# diskohedron4w_revd.net
KiCad netlist of a schematic drawn in EAGLE
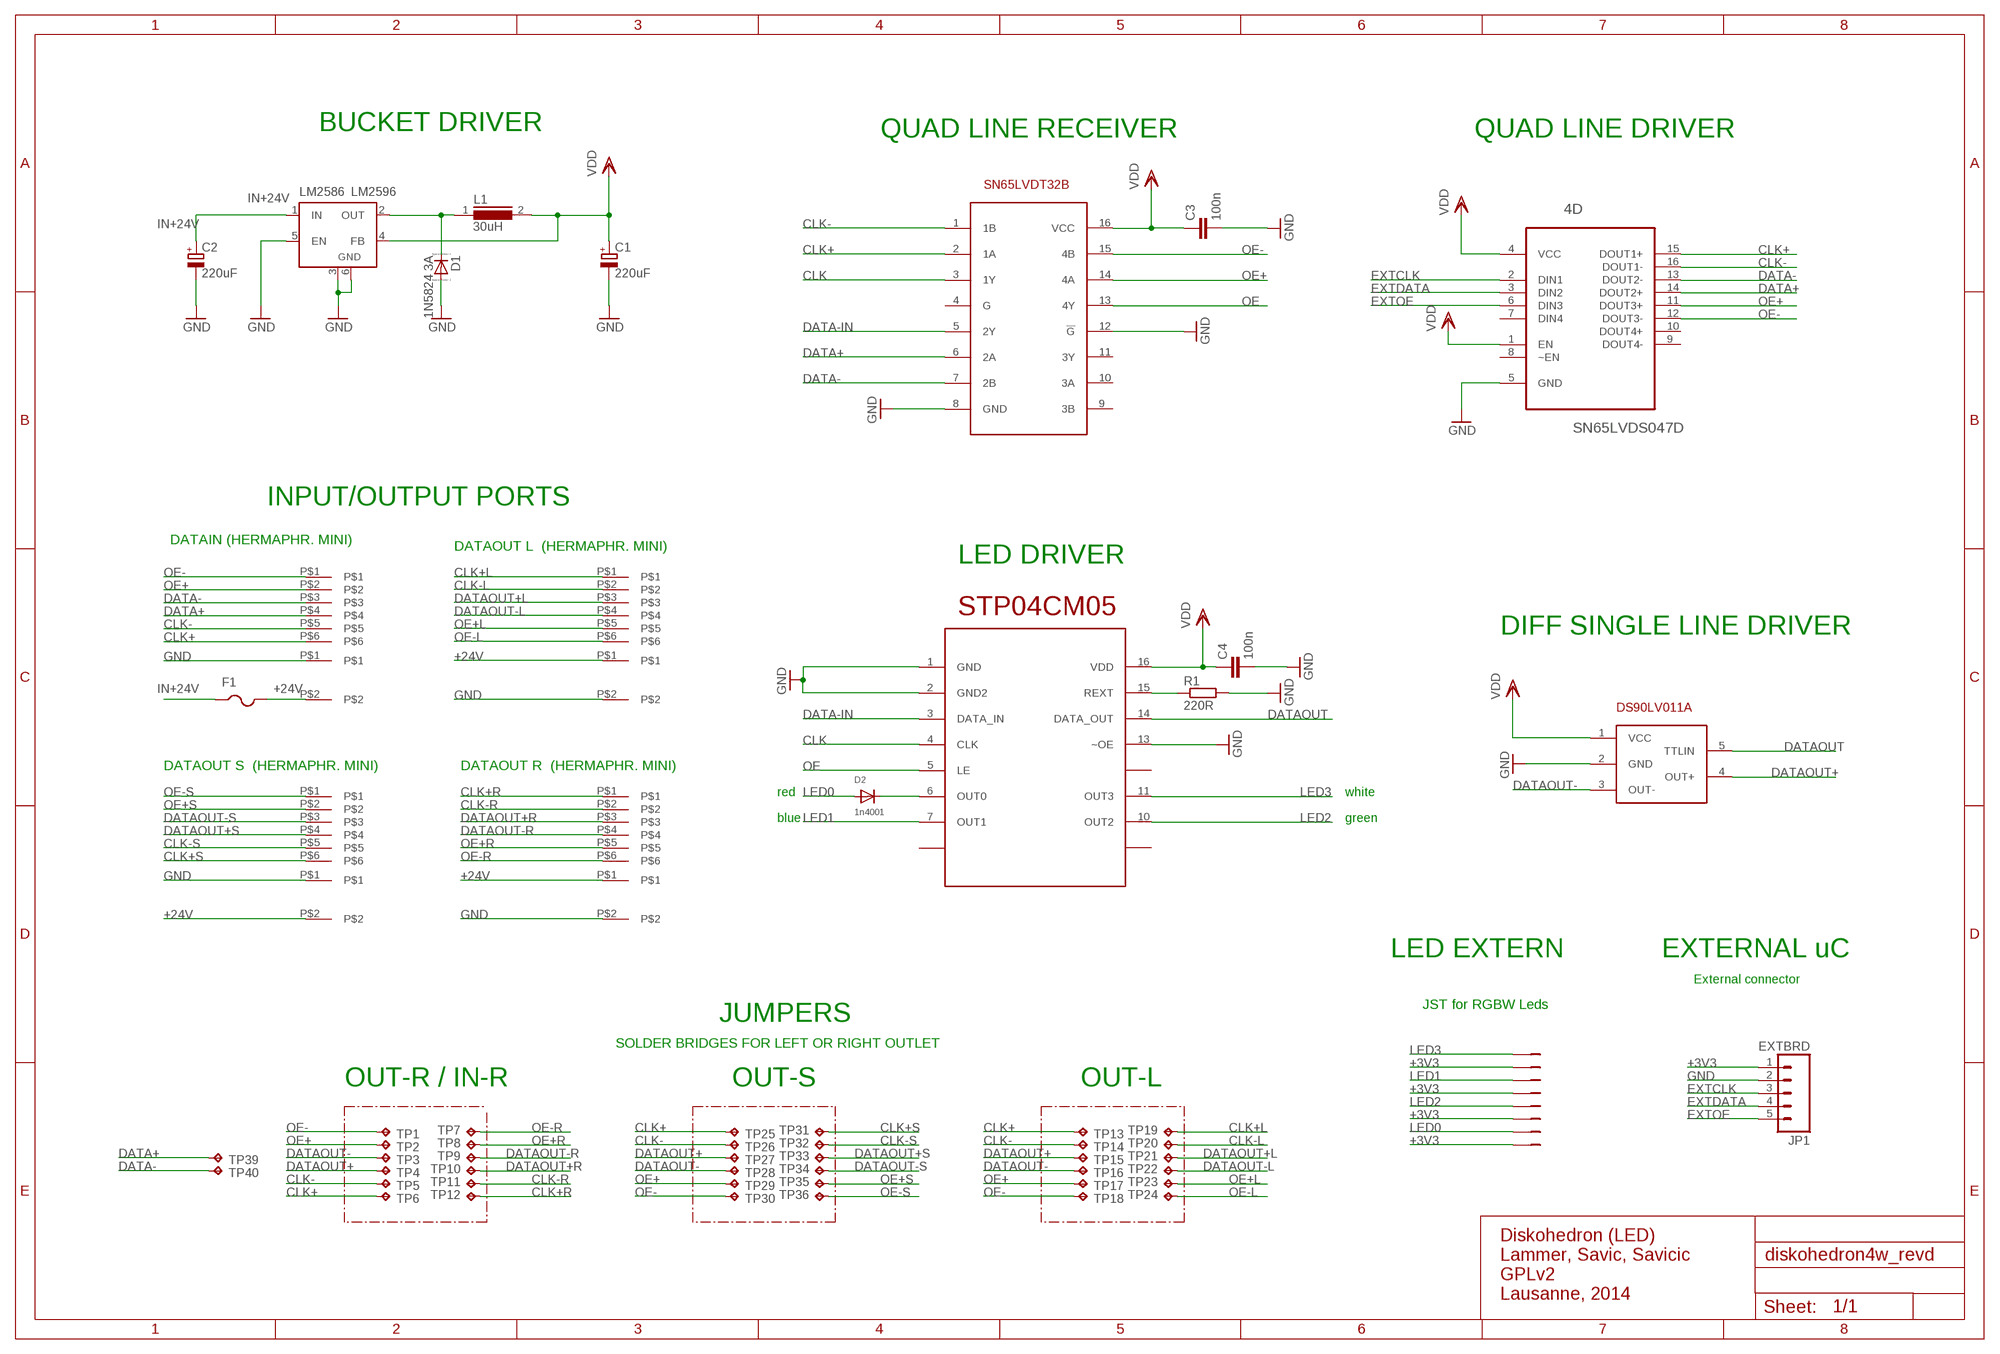
[diagram p0: schematic, sheet 1]

(export (version "E")
  (design (tool "Eeschema 10.0.6"))
  (components
    (comp (ref "1D")
      (value "DS90LV011A")
      (footprint "eagle-import:SOT23-5")
      (libsource (lib "eagle-import") (part "DS90LV011A"))
    )
    (comp (ref "4D")
      (value "SN65LVDS047D")
      (footprint "eagle-import:SOIC127P600X175-16N")
      (libsource (lib "eagle-import") (part "SN65LVDS047D"))
    )
    (comp (ref "4R")
      (value "SN65LVDST32")
      (footprint "eagle-import:SOIC16")
      (libsource (lib "eagle-import") (part "SN65LVDST32"))
    )
    (comp (ref "C1")
      (value "220uF")
      (footprint "eagle-import:175TMP-0810")
      (libsource (lib "eagle-import") (part "CPOL-EU175TMP-0810"))
    )
    (comp (ref "C2")
      (value "220uF")
      (footprint "eagle-import:175TMP-0810")
      (libsource (lib "eagle-import") (part "CPOL-EU175TMP-0810"))
    )
    (comp (ref "C3")
      (value "100n")
      (footprint "eagle-import:C0805")
      (libsource (lib "eagle-import") (part "C-EUC0805"))
    )
    (comp (ref "C4")
      (value "100n")
      (footprint "eagle-import:C0805")
      (libsource (lib "eagle-import") (part "C-EUC0805"))
    )
    (comp (ref "D1")
      (value "1N5824 3A")
      (footprint "eagle-import:DIODE_SMC")
      (libsource (lib "eagle-import") (part "DIODE_E-SMC"))
    )
    (comp (ref "D2")
      (value "1n4001")
      (footprint "eagle-import:SMADIODE")
      (libsource (lib "eagle-import") (part "DIODESMA"))
    )
    (comp (ref "F1")
      (value "PTCFUSE-1812")
      (footprint "eagle-import:1812")
      (libsource (lib "eagle-import") (part "PTCFUSE-1812"))
    )
    (comp (ref "IN1")
      (value "HERMAPHRODITMINI6PIN")
      (footprint "eagle-import:HERMAPHRODITMINI6PIN")
      (libsource (lib "eagle-import") (part "HERMAPHRODITMINI6PIN"))
    )
    (comp (ref "JP1")
      (value "EXTBRD")
      (footprint "eagle-import:1X05")
      (libsource (lib "eagle-import") (part "M05PTH"))
    )
    (comp (ref "JST")
      (value "8PIN-ZH")
      (footprint "eagle-import:B8B-ZH")
      (libsource (lib "eagle-import") (part "8PIN-ZH"))
    )
    (comp (ref "L1")
      (value "30uH")
      (footprint "eagle-import:DR127")
      (libsource (lib "eagle-import") (part "DR127"))
    )
    (comp (ref "LM2586")
      (value "LM2596")
      (footprint "eagle-import:TO263-5")
      (libsource (lib "eagle-import") (part "LM2596S"))
    )
    (comp (ref "OUT-L")
      (value "HERMAPHRODITMINI6PIN")
      (footprint "eagle-import:HERMAPHRODITMINI6PIN")
      (libsource (lib "eagle-import") (part "HERMAPHRODITMINI6PIN"))
    )
    (comp (ref "OUT-R")
      (value "HERMAPHRODITMINI6PIN")
      (footprint "eagle-import:HERMAPHRODITMINI6PIN")
      (libsource (lib "eagle-import") (part "HERMAPHRODITMINI6PIN"))
    )
    (comp (ref "OUT-R1")
      (value "HERMAPHRODITMINI6PIN")
      (footprint "eagle-import:HERMAPHRODITMINI6PIN")
      (libsource (lib "eagle-import") (part "HERMAPHRODITMINI6PIN"))
    )
    (comp (ref "R1")
      (value "220R")
      (footprint "eagle-import:M0805")
      (libsource (lib "eagle-import") (part "R-EU_M0805"))
    )
    (comp (ref "STP04")
      (value "STP04CM05")
      (footprint "eagle-import:TSSOP16")
      (libsource (lib "eagle-import") (part "STP04CM05"))
    )
    (comp (ref "TP1")
      (value "TPTP12SQ")
      (footprint "eagle-import:TP12SQ")
      (libsource (lib "eagle-import") (part "TPTP12SQ"))
    )
    (comp (ref "TP2")
      (value "TPTP12SQ")
      (footprint "eagle-import:TP12SQ")
      (libsource (lib "eagle-import") (part "TPTP12SQ"))
    )
    (comp (ref "TP3")
      (value "TPTP09SQ")
      (footprint "eagle-import:TP09SQ")
      (libsource (lib "eagle-import") (part "TPTP09SQ"))
    )
    (comp (ref "TP4")
      (value "TPTP09SQ")
      (footprint "eagle-import:TP09SQ")
      (libsource (lib "eagle-import") (part "TPTP09SQ"))
    )
    (comp (ref "TP5")
      (value "TPTP12SQ")
      (footprint "eagle-import:TP12SQ")
      (libsource (lib "eagle-import") (part "TPTP12SQ"))
    )
    (comp (ref "TP6")
      (value "TPTP12SQ")
      (footprint "eagle-import:TP12SQ")
      (libsource (lib "eagle-import") (part "TPTP12SQ"))
    )
    (comp (ref "TP7")
      (value "TPTP12SQ")
      (footprint "eagle-import:TP12SQ")
      (libsource (lib "eagle-import") (part "TPTP12SQ"))
    )
    (comp (ref "TP8")
      (value "TPTP12SQ")
      (footprint "eagle-import:TP12SQ")
      (libsource (lib "eagle-import") (part "TPTP12SQ"))
    )
    (comp (ref "TP9")
      (value "TPTP20SQ")
      (footprint "eagle-import:TP20SQ")
      (libsource (lib "eagle-import") (part "TPTP20SQ"))
    )
    (comp (ref "TP10")
      (value "TPTP20SQ")
      (footprint "eagle-import:TP20SQ")
      (libsource (lib "eagle-import") (part "TPTP20SQ"))
    )
    (comp (ref "TP11")
      (value "TPTP12SQ")
      (footprint "eagle-import:TP12SQ")
      (libsource (lib "eagle-import") (part "TPTP12SQ"))
    )
    (comp (ref "TP12")
      (value "TPTP12SQ")
      (footprint "eagle-import:TP12SQ")
      (libsource (lib "eagle-import") (part "TPTP12SQ"))
    )
    (comp (ref "TP13")
      (value "TPTP12SQ")
      (footprint "eagle-import:TP12SQ")
      (libsource (lib "eagle-import") (part "TPTP12SQ"))
    )
    (comp (ref "TP14")
      (value "TPTP12SQ")
      (footprint "eagle-import:TP12SQ")
      (libsource (lib "eagle-import") (part "TPTP12SQ"))
    )
    (comp (ref "TP15")
      (value "TPTP12SQ")
      (footprint "eagle-import:TP12SQ")
      (libsource (lib "eagle-import") (part "TPTP12SQ"))
    )
    (comp (ref "TP16")
      (value "TPTP12SQ")
      (footprint "eagle-import:TP12SQ")
      (libsource (lib "eagle-import") (part "TPTP12SQ"))
    )
    (comp (ref "TP17")
      (value "TPTP12SQ")
      (footprint "eagle-import:TP12SQ")
      (libsource (lib "eagle-import") (part "TPTP12SQ"))
    )
    (comp (ref "TP18")
      (value "TPTP12SQ")
      (footprint "eagle-import:TP12SQ")
      (libsource (lib "eagle-import") (part "TPTP12SQ"))
    )
    (comp (ref "TP19")
      (value "TPTP12SQ")
      (footprint "eagle-import:TP12SQ")
      (libsource (lib "eagle-import") (part "TPTP12SQ"))
    )
    (comp (ref "TP20")
      (value "TPTP12SQ")
      (footprint "eagle-import:TP12SQ")
      (libsource (lib "eagle-import") (part "TPTP12SQ"))
    )
    (comp (ref "TP21")
      (value "TPTP12SQ")
      (footprint "eagle-import:TP12SQ")
      (libsource (lib "eagle-import") (part "TPTP12SQ"))
    )
    (comp (ref "TP22")
      (value "TPTP12SQ")
      (footprint "eagle-import:TP12SQ")
      (libsource (lib "eagle-import") (part "TPTP12SQ"))
    )
    (comp (ref "TP23")
      (value "TPTP12SQ")
      (footprint "eagle-import:TP12SQ")
      (libsource (lib "eagle-import") (part "TPTP12SQ"))
    )
    (comp (ref "TP24")
      (value "TPTP12SQ")
      (footprint "eagle-import:TP12SQ")
      (libsource (lib "eagle-import") (part "TPTP12SQ"))
    )
    (comp (ref "TP25")
      (value "TPTP12SQ")
      (footprint "eagle-import:TP12SQ")
      (libsource (lib "eagle-import") (part "TPTP12SQ"))
    )
    (comp (ref "TP26")
      (value "TPTP12SQ")
      (footprint "eagle-import:TP12SQ")
      (libsource (lib "eagle-import") (part "TPTP12SQ"))
    )
    (comp (ref "TP27")
      (value "TPTP12SQ")
      (footprint "eagle-import:TP12SQ")
      (libsource (lib "eagle-import") (part "TPTP12SQ"))
    )
    (comp (ref "TP28")
      (value "TPTP12SQ")
      (footprint "eagle-import:TP12SQ")
      (libsource (lib "eagle-import") (part "TPTP12SQ"))
    )
    (comp (ref "TP29")
      (value "TPTP12SQ")
      (footprint "eagle-import:TP12SQ")
      (libsource (lib "eagle-import") (part "TPTP12SQ"))
    )
    (comp (ref "TP30")
      (value "TPTP12SQ")
      (footprint "eagle-import:TP12SQ")
      (libsource (lib "eagle-import") (part "TPTP12SQ"))
    )
    (comp (ref "TP31")
      (value "TPTP12SQ")
      (footprint "eagle-import:TP12SQ")
      (libsource (lib "eagle-import") (part "TPTP12SQ"))
    )
    (comp (ref "TP32")
      (value "TPTP12SQ")
      (footprint "eagle-import:TP12SQ")
      (libsource (lib "eagle-import") (part "TPTP12SQ"))
    )
    (comp (ref "TP33")
      (value "TPTP12SQ")
      (footprint "eagle-import:TP12SQ")
      (libsource (lib "eagle-import") (part "TPTP12SQ"))
    )
    (comp (ref "TP34")
      (value "TPTP12SQ")
      (footprint "eagle-import:TP12SQ")
      (libsource (lib "eagle-import") (part "TPTP12SQ"))
    )
    (comp (ref "TP35")
      (value "TPTP12SQ")
      (footprint "eagle-import:TP12SQ")
      (libsource (lib "eagle-import") (part "TPTP12SQ"))
    )
    (comp (ref "TP36")
      (value "TPTP12SQ")
      (footprint "eagle-import:TP12SQ")
      (libsource (lib "eagle-import") (part "TPTP12SQ"))
    )
    (comp (ref "TP39")
      (value "TPTP09SQ")
      (footprint "eagle-import:TP09SQ")
      (libsource (lib "eagle-import") (part "TPTP09SQ"))
    )
    (comp (ref "TP40")
      (value "TPTP09SQ")
      (footprint "eagle-import:TP09SQ")
      (libsource (lib "eagle-import") (part "TPTP09SQ"))
    )
    (comp (ref "U$1")
      (value "HERMAPHRODIT2PIN")
      (footprint "eagle-import:HERMAPHRODIT2PIN")
      (libsource (lib "eagle-import") (part "HERMAPHRODIT2PIN"))
    )
    (comp (ref "U$6")
      (value "HERMAPHRODIT2PIN")
      (footprint "eagle-import:HERMAPHRODIT2PIN")
      (libsource (lib "eagle-import") (part "HERMAPHRODIT2PIN"))
    )
    (comp (ref "U$7")
      (value "HERMAPHRODIT2PIN")
      (footprint "eagle-import:HERMAPHRODIT2PIN")
      (libsource (lib "eagle-import") (part "HERMAPHRODIT2PIN"))
    )
    (comp (ref "U$12")
      (value "HERMAPHRODIT2PIN")
      (footprint "eagle-import:HERMAPHRODIT2PIN")
      (libsource (lib "eagle-import") (part "HERMAPHRODIT2PIN"))
    )
  )
  (nets
    (net (code "1") (name "/+24V") (class "Default")
      (node (ref "F1") (pin "2") (pinfunction "2_2") (pintype "passive"))
      (node (ref "U$1") (pin "P$2") (pinfunction "P$2_P$2") (pintype "bidirectional"))
      (node (ref "U$12") (pin "P$1") (pinfunction "P$1_P$1") (pintype "bidirectional"))
      (node (ref "U$6") (pin "P$1") (pinfunction "P$1_P$1") (pintype "bidirectional"))
      (node (ref "U$7") (pin "P$2") (pinfunction "P$2_P$2") (pintype "bidirectional"))
    )
    (net (code "2") (name "/CLK") (class "Default")
      (node (ref "4R") (pin "3") (pinfunction "1Y_3") (pintype "bidirectional"))
      (node (ref "STP04") (pin "4") (pinfunction "CLK_4") (pintype "bidirectional"))
    )
    (net (code "3") (name "/CLK+") (class "Default")
      (node (ref "4D") (pin "15") (pinfunction "DOUT1+_15") (pintype "output"))
      (node (ref "4R") (pin "2") (pinfunction "1A_2") (pintype "bidirectional"))
      (node (ref "IN1") (pin "P$6") (pinfunction "P$6_P$6") (pintype "bidirectional"))
      (node (ref "TP13") (pin "TP") (pinfunction "TP_TP") (pintype "input"))
      (node (ref "TP25") (pin "TP") (pinfunction "TP_TP") (pintype "input"))
      (node (ref "TP6") (pin "TP") (pinfunction "TP_TP") (pintype "input"))
    )
    (net (code "4") (name "/CLK+L") (class "Default")
      (node (ref "OUT-L") (pin "P$1") (pinfunction "P$1_P$1") (pintype "bidirectional"))
      (node (ref "TP19") (pin "TP") (pinfunction "TP_TP") (pintype "input"))
    )
    (net (code "5") (name "/CLK+R") (class "Default")
      (node (ref "OUT-R") (pin "P$1") (pinfunction "P$1_P$1") (pintype "bidirectional"))
      (node (ref "TP12") (pin "TP") (pinfunction "TP_TP") (pintype "input"))
    )
    (net (code "6") (name "/CLK+S") (class "Default")
      (node (ref "OUT-R1") (pin "P$6") (pinfunction "P$6_P$6") (pintype "bidirectional"))
      (node (ref "TP31") (pin "TP") (pinfunction "TP_TP") (pintype "input"))
    )
    (net (code "7") (name "/CLK-") (class "Default")
      (node (ref "4D") (pin "16") (pinfunction "DOUT1-_16") (pintype "output"))
      (node (ref "4R") (pin "1") (pinfunction "1B_1") (pintype "bidirectional"))
      (node (ref "IN1") (pin "P$5") (pinfunction "P$5_P$5") (pintype "bidirectional"))
      (node (ref "TP14") (pin "TP") (pinfunction "TP_TP") (pintype "input"))
      (node (ref "TP26") (pin "TP") (pinfunction "TP_TP") (pintype "input"))
      (node (ref "TP5") (pin "TP") (pinfunction "TP_TP") (pintype "input"))
    )
    (net (code "8") (name "/CLK-L") (class "Default")
      (node (ref "OUT-L") (pin "P$2") (pinfunction "P$2_P$2") (pintype "bidirectional"))
      (node (ref "TP20") (pin "TP") (pinfunction "TP_TP") (pintype "input"))
    )
    (net (code "9") (name "/CLK-R") (class "Default")
      (node (ref "OUT-R") (pin "P$2") (pinfunction "P$2_P$2") (pintype "bidirectional"))
      (node (ref "TP11") (pin "TP") (pinfunction "TP_TP") (pintype "input"))
    )
    (net (code "10") (name "/CLK-S") (class "Default")
      (node (ref "OUT-R1") (pin "P$5") (pinfunction "P$5_P$5") (pintype "bidirectional"))
      (node (ref "TP32") (pin "TP") (pinfunction "TP_TP") (pintype "input"))
    )
    (net (code "11") (name "/DATA+") (class "Default")
      (node (ref "4D") (pin "14") (pinfunction "DOUT2+_14") (pintype "output"))
      (node (ref "4R") (pin "6") (pinfunction "2A_6") (pintype "bidirectional"))
      (node (ref "IN1") (pin "P$4") (pinfunction "P$4_P$4") (pintype "bidirectional"))
      (node (ref "TP39") (pin "TP") (pinfunction "TP_TP") (pintype "input"))
    )
    (net (code "12") (name "/DATA-") (class "Default")
      (node (ref "4D") (pin "13") (pinfunction "DOUT2-_13") (pintype "output"))
      (node (ref "4R") (pin "7") (pinfunction "2B_7") (pintype "bidirectional"))
      (node (ref "IN1") (pin "P$3") (pinfunction "P$3_P$3") (pintype "bidirectional"))
      (node (ref "TP40") (pin "TP") (pinfunction "TP_TP") (pintype "input"))
    )
    (net (code "13") (name "/DATA-IN") (class "Default")
      (node (ref "4R") (pin "5") (pinfunction "2Y_5") (pintype "bidirectional"))
      (node (ref "STP04") (pin "3") (pinfunction "DATA_IN_3") (pintype "bidirectional"))
    )
    (net (code "14") (name "/DATAOUT") (class "Default")
      (node (ref "1D") (pin "5") (pinfunction "TTLIN_5") (pintype "bidirectional"))
      (node (ref "STP04") (pin "14") (pinfunction "DATA_OUT_14") (pintype "bidirectional"))
    )
    (net (code "15") (name "/DATAOUT+") (class "Default")
      (node (ref "1D") (pin "4") (pinfunction "OUT+_4") (pintype "bidirectional"))
      (node (ref "TP15") (pin "TP") (pinfunction "TP_TP") (pintype "input"))
      (node (ref "TP27") (pin "TP") (pinfunction "TP_TP") (pintype "input"))
      (node (ref "TP4") (pin "TP") (pinfunction "TP_TP") (pintype "input"))
    )
    (net (code "16") (name "/DATAOUT+L") (class "Default")
      (node (ref "OUT-L") (pin "P$3") (pinfunction "P$3_P$3") (pintype "bidirectional"))
      (node (ref "TP21") (pin "TP") (pinfunction "TP_TP") (pintype "input"))
    )
    (net (code "17") (name "/DATAOUT+R") (class "Default")
      (node (ref "OUT-R") (pin "P$3") (pinfunction "P$3_P$3") (pintype "bidirectional"))
      (node (ref "TP10") (pin "TP") (pinfunction "TP_TP") (pintype "input"))
    )
    (net (code "18") (name "/DATAOUT+S") (class "Default")
      (node (ref "OUT-R1") (pin "P$4") (pinfunction "P$4_P$4") (pintype "bidirectional"))
      (node (ref "TP33") (pin "TP") (pinfunction "TP_TP") (pintype "input"))
    )
    (net (code "19") (name "/DATAOUT-") (class "Default")
      (node (ref "1D") (pin "3") (pinfunction "OUT-_3") (pintype "bidirectional"))
      (node (ref "TP16") (pin "TP") (pinfunction "TP_TP") (pintype "input"))
      (node (ref "TP28") (pin "TP") (pinfunction "TP_TP") (pintype "input"))
      (node (ref "TP3") (pin "TP") (pinfunction "TP_TP") (pintype "input"))
    )
    (net (code "20") (name "/DATAOUT-L") (class "Default")
      (node (ref "OUT-L") (pin "P$4") (pinfunction "P$4_P$4") (pintype "bidirectional"))
      (node (ref "TP22") (pin "TP") (pinfunction "TP_TP") (pintype "input"))
    )
    (net (code "21") (name "/DATAOUT-R") (class "Default")
      (node (ref "OUT-R") (pin "P$4") (pinfunction "P$4_P$4") (pintype "bidirectional"))
      (node (ref "TP9") (pin "TP") (pinfunction "TP_TP") (pintype "input"))
    )
    (net (code "22") (name "/DATAOUT-S") (class "Default")
      (node (ref "OUT-R1") (pin "P$3") (pinfunction "P$3_P$3") (pintype "bidirectional"))
      (node (ref "TP34") (pin "TP") (pinfunction "TP_TP") (pintype "input"))
    )
    (net (code "23") (name "/EXTCLK") (class "Default")
      (node (ref "4D") (pin "2") (pinfunction "DIN1_2") (pintype "input"))
      (node (ref "JP1") (pin "3") (pinfunction "3_3") (pintype "passive"))
    )
    (net (code "24") (name "/EXTDATA") (class "Default")
      (node (ref "4D") (pin "3") (pinfunction "DIN2_3") (pintype "input"))
      (node (ref "JP1") (pin "4") (pinfunction "4_4") (pintype "passive"))
    )
    (net (code "25") (name "/EXTOE") (class "Default")
      (node (ref "4D") (pin "6") (pinfunction "DIN3_6") (pintype "input"))
      (node (ref "JP1") (pin "5") (pinfunction "5_5") (pintype "passive"))
    )
    (net (code "26") (name "/IN+24V") (class "Default")
      (node (ref "C2") (pin "+") (pinfunction "+_+") (pintype "passive"))
      (node (ref "F1") (pin "1") (pinfunction "1_1") (pintype "passive"))
      (node (ref "LM2586") (pin "1") (pinfunction "IN_1") (pintype "input"))
    )
    (net (code "27") (name "/LED0") (class "Default")
      (node (ref "D2") (pin "A") (pinfunction "A_A") (pintype "passive"))
      (node (ref "JST") (pin "7") (pinfunction "1_7") (pintype "passive"))
    )
    (net (code "28") (name "/LED1") (class "Default")
      (node (ref "JST") (pin "3") (pinfunction "1_3") (pintype "passive"))
      (node (ref "STP04") (pin "7") (pinfunction "OUT1_7") (pintype "bidirectional"))
    )
    (net (code "29") (name "/LED2") (class "Default")
      (node (ref "JST") (pin "5") (pinfunction "1_5") (pintype "passive"))
      (node (ref "STP04") (pin "10") (pinfunction "OUT2_10") (pintype "bidirectional"))
    )
    (net (code "30") (name "/LED3") (class "Default")
      (node (ref "JST") (pin "1") (pinfunction "1_1") (pintype "passive"))
      (node (ref "STP04") (pin "11") (pinfunction "OUT3_11") (pintype "bidirectional"))
    )
    (net (code "31") (name "/OE") (class "Default")
      (node (ref "4R") (pin "13") (pinfunction "4Y_13") (pintype "bidirectional"))
      (node (ref "STP04") (pin "5") (pinfunction "LE_5") (pintype "bidirectional"))
    )
    (net (code "32") (name "/OE+") (class "Default")
      (node (ref "4D") (pin "11") (pinfunction "DOUT3+_11") (pintype "output"))
      (node (ref "4R") (pin "14") (pinfunction "4A_14") (pintype "bidirectional"))
      (node (ref "IN1") (pin "P$2") (pinfunction "P$2_P$2") (pintype "bidirectional"))
      (node (ref "TP17") (pin "TP") (pinfunction "TP_TP") (pintype "input"))
      (node (ref "TP2") (pin "TP") (pinfunction "TP_TP") (pintype "input"))
      (node (ref "TP29") (pin "TP") (pinfunction "TP_TP") (pintype "input"))
    )
    (net (code "33") (name "/OE+L") (class "Default")
      (node (ref "OUT-L") (pin "P$5") (pinfunction "P$5_P$5") (pintype "bidirectional"))
      (node (ref "TP23") (pin "TP") (pinfunction "TP_TP") (pintype "input"))
    )
    (net (code "34") (name "/OE+R") (class "Default")
      (node (ref "OUT-R") (pin "P$5") (pinfunction "P$5_P$5") (pintype "bidirectional"))
      (node (ref "TP8") (pin "TP") (pinfunction "TP_TP") (pintype "input"))
    )
    (net (code "35") (name "/OE+S") (class "Default")
      (node (ref "OUT-R1") (pin "P$2") (pinfunction "P$2_P$2") (pintype "bidirectional"))
      (node (ref "TP35") (pin "TP") (pinfunction "TP_TP") (pintype "input"))
    )
    (net (code "36") (name "/OE-") (class "Default")
      (node (ref "4D") (pin "12") (pinfunction "DOUT3-_12") (pintype "output"))
      (node (ref "4R") (pin "15") (pinfunction "4B_15") (pintype "bidirectional"))
      (node (ref "IN1") (pin "P$1") (pinfunction "P$1_P$1") (pintype "bidirectional"))
      (node (ref "TP1") (pin "TP") (pinfunction "TP_TP") (pintype "input"))
      (node (ref "TP18") (pin "TP") (pinfunction "TP_TP") (pintype "input"))
      (node (ref "TP30") (pin "TP") (pinfunction "TP_TP") (pintype "input"))
    )
    (net (code "37") (name "/OE-L") (class "Default")
      (node (ref "OUT-L") (pin "P$6") (pinfunction "P$6_P$6") (pintype "bidirectional"))
      (node (ref "TP24") (pin "TP") (pinfunction "TP_TP") (pintype "input"))
    )
    (net (code "38") (name "/OE-R") (class "Default")
      (node (ref "OUT-R") (pin "P$6") (pinfunction "P$6_P$6") (pintype "bidirectional"))
      (node (ref "TP7") (pin "TP") (pinfunction "TP_TP") (pintype "input"))
    )
    (net (code "39") (name "/OE-S") (class "Default")
      (node (ref "OUT-R1") (pin "P$1") (pinfunction "P$1_P$1") (pintype "bidirectional"))
      (node (ref "TP36") (pin "TP") (pinfunction "TP_TP") (pintype "input"))
    )
    (net (code "40") (name "GND") (class "Default")
      (node (ref "1D") (pin "2") (pinfunction "GND_2") (pintype "bidirectional"))
      (node (ref "4D") (pin "5") (pinfunction "GND_5") (pintype "passive"))
      (node (ref "4R") (pin "12") (pinfunction "~{G}_12") (pintype "bidirectional"))
      (node (ref "4R") (pin "8") (pinfunction "GND_8") (pintype "bidirectional"))
      (node (ref "C1") (pin "-") (pinfunction "-_-") (pintype "passive"))
      (node (ref "C2") (pin "-") (pinfunction "-_-") (pintype "passive"))
      (node (ref "C3") (pin "2") (pinfunction "2_2") (pintype "passive"))
      (node (ref "C4") (pin "2") (pinfunction "2_2") (pintype "passive"))
      (node (ref "D1") (pin "A") (pinfunction "C_A") (pintype "passive"))
      (node (ref "JP1") (pin "2") (pinfunction "2_2") (pintype "passive"))
      (node (ref "LM2586") (pin "3") (pinfunction "GND_3") (pintype "power_in"))
      (node (ref "LM2586") (pin "5") (pinfunction "EN_5") (pintype "input"))
      (node (ref "LM2586") (pin "6") (pinfunction "GND_6") (pintype "power_in"))
      (node (ref "R1") (pin "2") (pinfunction "2_2") (pintype "passive"))
      (node (ref "STP04") (pin "1") (pinfunction "GND_1") (pintype "bidirectional"))
      (node (ref "STP04") (pin "13") (pinfunction "~{OE}_13") (pintype "bidirectional"))
      (node (ref "STP04") (pin "2") (pinfunction "GND2_2") (pintype "bidirectional"))
      (node (ref "U$1") (pin "P$1") (pinfunction "P$1_P$1") (pintype "bidirectional"))
      (node (ref "U$12") (pin "P$2") (pinfunction "P$2_P$2") (pintype "bidirectional"))
      (node (ref "U$6") (pin "P$2") (pinfunction "P$2_P$2") (pintype "bidirectional"))
      (node (ref "U$7") (pin "P$1") (pinfunction "P$1_P$1") (pintype "bidirectional"))
    )
    (net (code "41") (name "Net-(D1-A)") (class "Default")
      (node (ref "D1") (pin "C") (pinfunction "A_C") (pintype "passive"))
      (node (ref "L1") (pin "1") (pinfunction "1_1") (pintype "passive"))
      (node (ref "LM2586") (pin "2") (pinfunction "OUT_2") (pintype "output"))
    )
    (net (code "42") (name "Net-(STP04-OUT0)") (class "Default")
      (node (ref "D2") (pin "C") (pinfunction "C_C") (pintype "passive"))
      (node (ref "STP04") (pin "6") (pinfunction "OUT0_6") (pintype "bidirectional"))
    )
    (net (code "43") (name "Net-(STP04-REXT)") (class "Default")
      (node (ref "R1") (pin "1") (pinfunction "1_1") (pintype "passive"))
      (node (ref "STP04") (pin "15") (pinfunction "REXT_15") (pintype "bidirectional"))
    )
    (net (code "44") (name "VDD") (class "Default")
      (node (ref "1D") (pin "1") (pinfunction "VCC_1") (pintype "bidirectional"))
      (node (ref "4D") (pin "1") (pinfunction "EN_1") (pintype "input"))
      (node (ref "4D") (pin "4") (pinfunction "VCC_4") (pintype "power_in"))
      (node (ref "4R") (pin "16") (pinfunction "VCC_16") (pintype "bidirectional"))
      (node (ref "C1") (pin "+") (pinfunction "+_+") (pintype "passive"))
      (node (ref "C3") (pin "1") (pinfunction "1_1") (pintype "passive"))
      (node (ref "C4") (pin "1") (pinfunction "1_1") (pintype "passive"))
      (node (ref "JP1") (pin "1") (pinfunction "1_1") (pintype "passive"))
      (node (ref "JST") (pin "2") (pinfunction "1_2") (pintype "passive"))
      (node (ref "JST") (pin "4") (pinfunction "1_4") (pintype "passive"))
      (node (ref "JST") (pin "6") (pinfunction "1_6") (pintype "passive"))
      (node (ref "JST") (pin "8") (pinfunction "1_8") (pintype "passive"))
      (node (ref "L1") (pin "2") (pinfunction "2_2") (pintype "passive"))
      (node (ref "LM2586") (pin "4") (pinfunction "FB_4") (pintype "input"))
      (node (ref "STP04") (pin "16") (pinfunction "VDD_16") (pintype "bidirectional"))
    )
    (net (code "45") (name "unconnected-(4D-DIN4-Pad7)") (class "Default")
      (node (ref "4D") (pin "7") (pinfunction "DIN4_7") (pintype "input"))
    )
    (net (code "46") (name "unconnected-(4D-DOUT4+-Pad10)") (class "Default")
      (node (ref "4D") (pin "10") (pinfunction "DOUT4+_10") (pintype "output"))
    )
    (net (code "47") (name "unconnected-(4D-DOUT4--Pad9)") (class "Default")
      (node (ref "4D") (pin "9") (pinfunction "DOUT4-_9") (pintype "output"))
    )
    (net (code "48") (name "unconnected-(4D-~{EN}-Pad8)") (class "Default")
      (node (ref "4D") (pin "8") (pinfunction "~{EN}_8") (pintype "input"))
    )
    (net (code "49") (name "unconnected-(4R-3A-Pad10)") (class "Default")
      (node (ref "4R") (pin "10") (pinfunction "3A_10") (pintype "bidirectional"))
    )
    (net (code "50") (name "unconnected-(4R-3B-Pad9)") (class "Default")
      (node (ref "4R") (pin "9") (pinfunction "3B_9") (pintype "bidirectional"))
    )
    (net (code "51") (name "unconnected-(4R-3Y-Pad11)") (class "Default")
      (node (ref "4R") (pin "11") (pinfunction "3Y_11") (pintype "bidirectional"))
    )
    (net (code "52") (name "unconnected-(4R-G-Pad4)") (class "Default")
      (node (ref "4R") (pin "4") (pinfunction "G_4") (pintype "bidirectional"))
    )
    (net (code "53") (name "unconnected-(STP04-N.C1-Pad8)") (class "Default")
      (node (ref "STP04") (pin "8") (pinfunction "N.C1_8") (pintype "bidirectional"))
    )
    (net (code "54") (name "unconnected-(STP04-NC-Pad9)") (class "Default")
      (node (ref "STP04") (pin "9") (pinfunction "NC_9") (pintype "bidirectional"))
    )
    (net (code "55") (name "unconnected-(STP04-NC3-Pad12)") (class "Default")
      (node (ref "STP04") (pin "12") (pinfunction "NC3_12") (pintype "bidirectional"))
    )
  )
)
